# res15_board.net
KiCad netlist of a schematic drawn in EAGLE
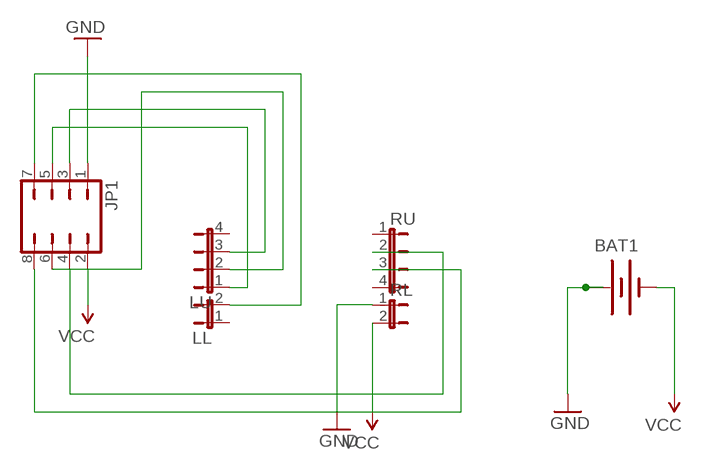
[diagram p0: schematic, sheet 1]

(export (version "E")
  (design (tool "Eeschema 10.0.6"))
  (components
    (comp (ref "BAT1")
      (value "BATTERY245MM")
      (footprint "eagle-import:BATTCON_245MM")
      (libsource (lib "eagle-import") (part "BATTERY245MM"))
    )
    (comp (ref "JP1")
      (value "JP4Q")
      (footprint "eagle-import:JP4Q")
      (libsource (lib "eagle-import") (part "JP4Q"))
    )
    (comp (ref "LL")
      (value "JP1E")
      (footprint "eagle-import:JP1")
      (libsource (lib "eagle-import") (part "JP1E"))
    )
    (comp (ref "LU")
      (value "JP4E")
      (footprint "eagle-import:JP4")
      (libsource (lib "eagle-import") (part "JP4E"))
    )
    (comp (ref "RL")
      (value "JP1E")
      (footprint "eagle-import:JP1")
      (libsource (lib "eagle-import") (part "JP1E"))
    )
    (comp (ref "RU")
      (value "JP4E")
      (footprint "eagle-import:JP4")
      (libsource (lib "eagle-import") (part "JP4E"))
    )
  )
  (nets
    (net (code "1") (name "GND") (class "Default")
      (node (ref "BAT1") (pin "1") (pinfunction "+_1") (pintype "power_in"))
      (node (ref "JP1") (pin "1") (pinfunction "1_1") (pintype "passive"))
      (node (ref "RL") (pin "1") (pinfunction "1_1") (pintype "passive"))
    )
    (net (code "2") (name "Net-(JP1-Pad3)") (class "Default")
      (node (ref "JP1") (pin "3") (pinfunction "3_3") (pintype "passive"))
      (node (ref "LU") (pin "3") (pinfunction "3_3") (pintype "passive"))
    )
    (net (code "3") (name "Net-(JP1-Pad4)") (class "Default")
      (node (ref "JP1") (pin "4") (pinfunction "4_4") (pintype "passive"))
      (node (ref "RU") (pin "2") (pinfunction "2_2") (pintype "passive"))
    )
    (net (code "4") (name "Net-(JP1-Pad5)") (class "Default")
      (node (ref "JP1") (pin "5") (pinfunction "5_5") (pintype "passive"))
      (node (ref "LU") (pin "1") (pinfunction "1_1") (pintype "passive"))
    )
    (net (code "5") (name "Net-(JP1-Pad6)") (class "Default")
      (node (ref "JP1") (pin "6") (pinfunction "6_6") (pintype "passive"))
      (node (ref "LU") (pin "2") (pinfunction "2_2") (pintype "passive"))
    )
    (net (code "6") (name "Net-(JP1-Pad7)") (class "Default")
      (node (ref "JP1") (pin "7") (pinfunction "7_7") (pintype "passive"))
      (node (ref "LL") (pin "2") (pinfunction "2_2") (pintype "passive"))
    )
    (net (code "7") (name "Net-(JP1-Pad8)") (class "Default")
      (node (ref "JP1") (pin "8") (pinfunction "8_8") (pintype "passive"))
      (node (ref "RU") (pin "3") (pinfunction "3_3") (pintype "passive"))
    )
    (net (code "8") (name "VCC") (class "Default")
      (node (ref "BAT1") (pin "2") (pinfunction "-_2") (pintype "power_in"))
      (node (ref "JP1") (pin "2") (pinfunction "2_2") (pintype "passive"))
      (node (ref "RL") (pin "2") (pinfunction "2_2") (pintype "passive"))
    )
    (net (code "9") (name "unconnected-(LL-Pad1)") (class "Default")
      (node (ref "LL") (pin "1") (pinfunction "1_1") (pintype "passive"))
    )
    (net (code "10") (name "unconnected-(LU-Pad4)") (class "Default")
      (node (ref "LU") (pin "4") (pinfunction "4_4") (pintype "passive"))
    )
    (net (code "11") (name "unconnected-(RU-Pad1)") (class "Default")
      (node (ref "RU") (pin "1") (pinfunction "1_1") (pintype "passive"))
    )
    (net (code "12") (name "unconnected-(RU-Pad4)") (class "Default")
      (node (ref "RU") (pin "4") (pinfunction "4_4") (pintype "passive"))
    )
  )
)
